# potencia.net
KiCad netlist of a schematic drawn in EAGLE
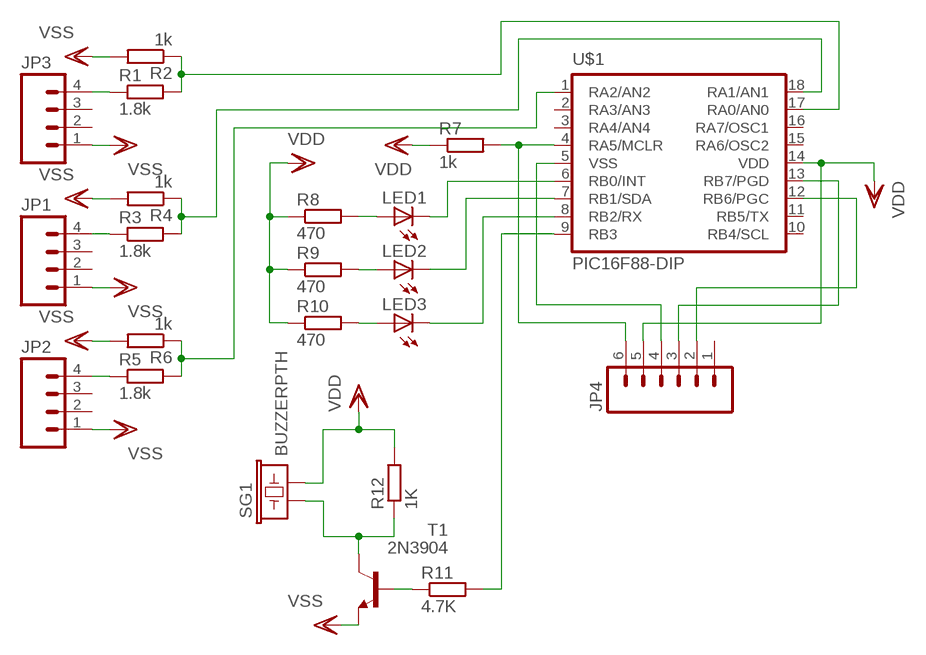
[diagram p0: schematic, sheet 1]
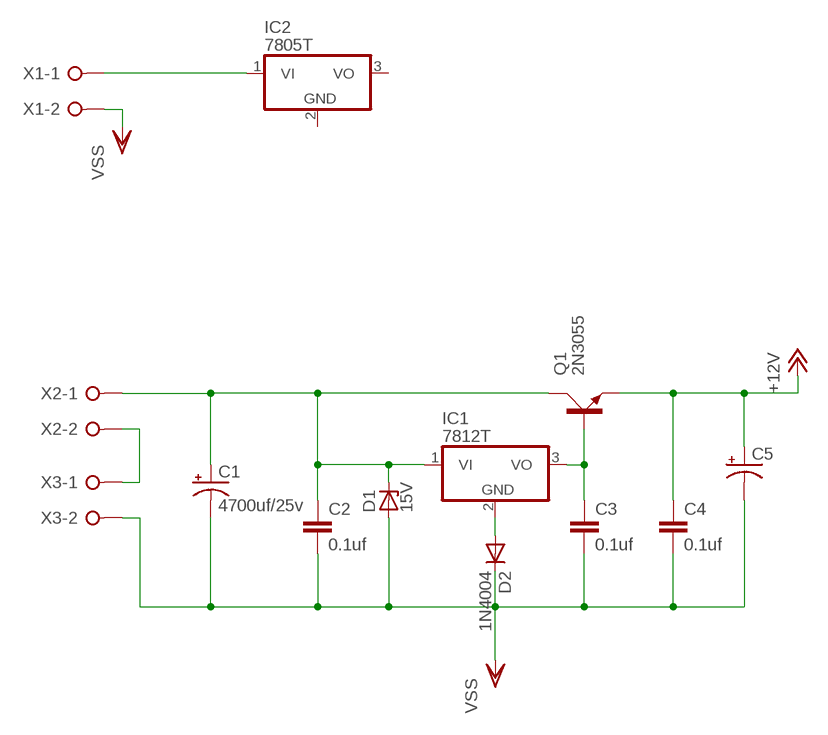
[diagram p1: schematic, sheet 2]

(export (version "E")
  (design (tool "Eeschema 10.0.6"))
  (components
    (comp (ref "C1")
      (value "4700uf/25v")
      (footprint "eagle-import:EB30D")
      (libsource (lib "eagle-import") (part "CPOL-USE10-30"))
    )
    (comp (ref "C2")
      (value "0.1uf")
      (footprint "eagle-import:C050-024X044")
      (libsource (lib "eagle-import") (part "C-EU050-024X044"))
    )
    (comp (ref "C3")
      (value "0.1uf")
      (footprint "eagle-import:C050-024X044")
      (libsource (lib "eagle-import") (part "C-EU050-024X044"))
    )
    (comp (ref "C4")
      (value "0.1uf")
      (footprint "eagle-import:C050-024X044")
      (libsource (lib "eagle-import") (part "C-EU050-024X044"))
    )
    (comp (ref "C5")
      (value "CPOL-USE2.5-6")
      (footprint "eagle-import:E2,5-6")
      (libsource (lib "eagle-import") (part "CPOL-USE2.5-6"))
    )
    (comp (ref "D1")
      (value "15V")
      (footprint "eagle-import:F126Z10")
      (libsource (lib "eagle-import") (part "ZENER-DIODEF126-10"))
    )
    (comp (ref "D2")
      (value "1N4004")
      (footprint "eagle-import:DO41-10")
      (libsource (lib "eagle-import") (part "1N4004"))
    )
    (comp (ref "IC1")
      (value "7812T")
      (footprint "eagle-import:TO220H")
      (libsource (lib "eagle-import") (part "78T12"))
    )
    (comp (ref "IC2")
      (value "7805T")
      (footprint "eagle-import:TO220H")
      (libsource (lib "eagle-import") (part "78T05"))
    )
    (comp (ref "Q1")
      (value "2N3055")
      (footprint "eagle-import:TO3A")
      (libsource (lib "eagle-import") (part "2N3055"))
    )
    (comp (ref "X1")
      (value "W237-2N")
      (footprint "eagle-import:W237-2N")
      (libsource (lib "eagle-import") (part "W237-2N"))
    )
    (comp (ref "X2")
      (value "W237-2N")
      (footprint "eagle-import:W237-2N")
      (libsource (lib "eagle-import") (part "W237-2N"))
    )
    (comp (ref "X3")
      (value "W237-2N")
      (footprint "eagle-import:W237-2N")
      (libsource (lib "eagle-import") (part "W237-2N"))
    )
    (comp (ref "JP1")
      (value "M04LONGPADS")
      (footprint "eagle-import:1X04_LONGPADS")
      (libsource (lib "eagle-import") (part "M04LONGPADS"))
    )
    (comp (ref "JP2")
      (value "M04LONGPADS")
      (footprint "eagle-import:1X04_LONGPADS")
      (libsource (lib "eagle-import") (part "M04LONGPADS"))
    )
    (comp (ref "JP3")
      (value "M04LONGPADS")
      (footprint "eagle-import:1X04_LONGPADS")
      (libsource (lib "eagle-import") (part "M04LONGPADS"))
    )
    (comp (ref "JP4")
      (value "M06LONGPADS")
      (footprint "eagle-import:1X06_LONGPADS")
      (libsource (lib "eagle-import") (part "M06LONGPADS"))
    )
    (comp (ref "LED1")
      (value "LED3MM")
      (footprint "eagle-import:LED3MM")
      (libsource (lib "eagle-import") (part "LED3MM"))
    )
    (comp (ref "LED2")
      (value "LED3MM")
      (footprint "eagle-import:LED3MM")
      (libsource (lib "eagle-import") (part "LED3MM"))
    )
    (comp (ref "LED3")
      (value "LED3MM")
      (footprint "eagle-import:LED3MM")
      (libsource (lib "eagle-import") (part "LED3MM"))
    )
    (comp (ref "R1")
      (value "1.8k")
      (footprint "eagle-import:0204_5")
      (libsource (lib "eagle-import") (part "R-EU_0204/5"))
    )
    (comp (ref "R2")
      (value "1k")
      (footprint "eagle-import:0204_5")
      (libsource (lib "eagle-import") (part "R-EU_0204/5"))
    )
    (comp (ref "R3")
      (value "1.8k")
      (footprint "eagle-import:0204_5")
      (libsource (lib "eagle-import") (part "R-EU_0204/5"))
    )
    (comp (ref "R4")
      (value "1k")
      (footprint "eagle-import:0204_5")
      (libsource (lib "eagle-import") (part "R-EU_0204/5"))
    )
    (comp (ref "R5")
      (value "1.8k")
      (footprint "eagle-import:0204_5")
      (libsource (lib "eagle-import") (part "R-EU_0204/5"))
    )
    (comp (ref "R6")
      (value "1k")
      (footprint "eagle-import:0204_5")
      (libsource (lib "eagle-import") (part "R-EU_0204/5"))
    )
    (comp (ref "R7")
      (value "1k")
      (footprint "eagle-import:0204_5")
      (libsource (lib "eagle-import") (part "R-EU_0204/5"))
    )
    (comp (ref "R8")
      (value "470")
      (footprint "eagle-import:0204_5")
      (libsource (lib "eagle-import") (part "R-EU_0204/5"))
    )
    (comp (ref "R9")
      (value "470")
      (footprint "eagle-import:0204_5")
      (libsource (lib "eagle-import") (part "R-EU_0204/5"))
    )
    (comp (ref "R10")
      (value "470")
      (footprint "eagle-import:0204_5")
      (libsource (lib "eagle-import") (part "R-EU_0204/5"))
    )
    (comp (ref "R11")
      (value "4.7K")
      (footprint "eagle-import:0204_5")
      (libsource (lib "eagle-import") (part "R-EU_0204/5"))
    )
    (comp (ref "R12")
      (value "1K")
      (footprint "eagle-import:0204_5")
      (libsource (lib "eagle-import") (part "R-EU_0204/5"))
    )
    (comp (ref "SG1")
      (value "BUZZERPTH")
      (footprint "eagle-import:BUZZER-12MM")
      (libsource (lib "eagle-import") (part "BUZZERPTH"))
    )
    (comp (ref "T1")
      (value "2N3904")
      (footprint "eagle-import:TO92")
      (libsource (lib "eagle-import") (part "2N3904"))
    )
    (comp (ref "U$1")
      (value "PIC16F88-DIP")
      (footprint "eagle-import:DIL18")
      (libsource (lib "eagle-import") (part "PIC16F88-DIP"))
    )
  )
  (nets
    (net (code "1") (name "+12V") (class "Default")
      (node (ref "C4") (pin "1") (pinfunction "1_1") (pintype "passive"))
      (node (ref "C5") (pin "+") (pinfunction "+_+") (pintype "passive"))
      (node (ref "Q1") (pin "E") (pinfunction "E_E") (pintype "passive"))
    )
    (net (code "2") (name "Net-(IC1-GND)") (class "Default")
      (node (ref "D2") (pin "A") (pinfunction "A_A") (pintype "passive"))
      (node (ref "IC1") (pin "2") (pinfunction "GND_2") (pintype "passive"))
    )
    (net (code "3") (name "Net-(IC1-VI)") (class "Default")
      (node (ref "C1") (pin "+") (pinfunction "+_+") (pintype "passive"))
      (node (ref "C2") (pin "1") (pinfunction "1_1") (pintype "passive"))
      (node (ref "D1") (pin "C") (pinfunction "C_C") (pintype "passive"))
      (node (ref "IC1") (pin "1") (pinfunction "VI_1") (pintype "input"))
      (node (ref "Q1") (pin "C") (pinfunction "C_C") (pintype "passive"))
      (node (ref "Q1") (pin "C1") (pinfunction "C_C1") (pintype "passive"))
      (node (ref "X2") (pin "1") (pinfunction "KL_1") (pintype "passive"))
    )
    (net (code "4") (name "Net-(IC1-VO)") (class "Default")
      (node (ref "C3") (pin "1") (pinfunction "1_1") (pintype "passive"))
      (node (ref "IC1") (pin "3") (pinfunction "VO_3") (pintype "passive"))
      (node (ref "Q1") (pin "B") (pinfunction "B_B") (pintype "passive"))
    )
    (net (code "5") (name "Net-(IC2-VI)") (class "Default")
      (node (ref "IC2") (pin "1") (pinfunction "VI_1") (pintype "input"))
      (node (ref "X1") (pin "1") (pinfunction "KL_1") (pintype "passive"))
    )
    (net (code "6") (name "Net-(JP1-Pad4)") (class "Default")
      (node (ref "JP1") (pin "4") (pinfunction "4_4") (pintype "passive"))
      (node (ref "R3") (pin "1") (pinfunction "1_1") (pintype "passive"))
    )
    (net (code "7") (name "Net-(JP2-Pad4)") (class "Default")
      (node (ref "JP2") (pin "4") (pinfunction "4_4") (pintype "passive"))
      (node (ref "R5") (pin "1") (pinfunction "1_1") (pintype "passive"))
    )
    (net (code "8") (name "Net-(JP3-Pad4)") (class "Default")
      (node (ref "JP3") (pin "4") (pinfunction "4_4") (pintype "passive"))
      (node (ref "R1") (pin "1") (pinfunction "1_1") (pintype "passive"))
    )
    (net (code "9") (name "Net-(LED1-C)") (class "Default")
      (node (ref "LED1") (pin "K") (pinfunction "C_K") (pintype "passive"))
      (node (ref "U$1") (pin "6") (pinfunction "RB0/INT_6") (pintype "bidirectional"))
    )
    (net (code "10") (name "Net-(LED1-PadA)") (class "Default")
      (node (ref "LED1") (pin "A") (pinfunction "A_A") (pintype "passive"))
      (node (ref "R8") (pin "2") (pinfunction "2_2") (pintype "passive"))
    )
    (net (code "11") (name "Net-(LED2-C)") (class "Default")
      (node (ref "LED2") (pin "K") (pinfunction "C_K") (pintype "passive"))
      (node (ref "U$1") (pin "7") (pinfunction "RB1/SDA_7") (pintype "bidirectional"))
    )
    (net (code "12") (name "Net-(LED2-PadA)") (class "Default")
      (node (ref "LED2") (pin "A") (pinfunction "A_A") (pintype "passive"))
      (node (ref "R9") (pin "2") (pinfunction "2_2") (pintype "passive"))
    )
    (net (code "13") (name "Net-(LED3-C)") (class "Default")
      (node (ref "LED3") (pin "K") (pinfunction "C_K") (pintype "passive"))
      (node (ref "U$1") (pin "8") (pinfunction "RB2/RX_8") (pintype "bidirectional"))
    )
    (net (code "14") (name "Net-(LED3-PadA)") (class "Default")
      (node (ref "LED3") (pin "A") (pinfunction "A_A") (pintype "passive"))
      (node (ref "R10") (pin "2") (pinfunction "2_2") (pintype "passive"))
    )
    (net (code "15") (name "Net-(SG1-1)") (class "Default")
      (node (ref "R12") (pin "1") (pinfunction "1_1") (pintype "passive"))
      (node (ref "SG1") (pin "+") (pinfunction "1_+") (pintype "passive"))
      (node (ref "T1") (pin "1") (pinfunction "C_1") (pintype "passive"))
    )
    (net (code "16") (name "Net-(T1-B)") (class "Default")
      (node (ref "R11") (pin "1") (pinfunction "1_1") (pintype "passive"))
      (node (ref "T1") (pin "2") (pinfunction "B_2") (pintype "passive"))
    )
    (net (code "17") (name "Net-(U$1-RA0{slash}AN0)") (class "Default")
      (node (ref "R1") (pin "2") (pinfunction "2_2") (pintype "passive"))
      (node (ref "R2") (pin "1") (pinfunction "1_1") (pintype "passive"))
      (node (ref "U$1") (pin "17") (pinfunction "RA0/AN0_17") (pintype "bidirectional"))
    )
    (net (code "18") (name "Net-(U$1-RA1{slash}AN1)") (class "Default")
      (node (ref "R3") (pin "2") (pinfunction "2_2") (pintype "passive"))
      (node (ref "R4") (pin "1") (pinfunction "1_1") (pintype "passive"))
      (node (ref "U$1") (pin "18") (pinfunction "RA1/AN1_18") (pintype "bidirectional"))
    )
    (net (code "19") (name "Net-(U$1-RA2{slash}AN2)") (class "Default")
      (node (ref "R5") (pin "2") (pinfunction "2_2") (pintype "passive"))
      (node (ref "R6") (pin "1") (pinfunction "1_1") (pintype "passive"))
      (node (ref "U$1") (pin "1") (pinfunction "RA2/AN2_1") (pintype "bidirectional"))
    )
    (net (code "20") (name "Net-(U$1-RA5{slash}MCLR)") (class "Default")
      (node (ref "JP4") (pin "6") (pinfunction "6_6") (pintype "passive"))
      (node (ref "R7") (pin "2") (pinfunction "2_2") (pintype "passive"))
      (node (ref "U$1") (pin "4") (pinfunction "RA5/MCLR_4") (pintype "input"))
    )
    (net (code "21") (name "Net-(U$1-RB3)") (class "Default")
      (node (ref "R11") (pin "2") (pinfunction "2_2") (pintype "passive"))
      (node (ref "U$1") (pin "9") (pinfunction "RB3_9") (pintype "bidirectional"))
    )
    (net (code "22") (name "Net-(U$1-RB6{slash}PGC)") (class "Default")
      (node (ref "JP4") (pin "2") (pinfunction "2_2") (pintype "passive"))
      (node (ref "U$1") (pin "12") (pinfunction "RB6/PGC_12") (pintype "bidirectional"))
    )
    (net (code "23") (name "Net-(U$1-RB7{slash}PGD)") (class "Default")
      (node (ref "JP4") (pin "3") (pinfunction "3_3") (pintype "passive"))
      (node (ref "U$1") (pin "13") (pinfunction "RB7/PGD_13") (pintype "bidirectional"))
    )
    (net (code "24") (name "Net-(U$1-VSS)") (class "Default")
      (node (ref "JP4") (pin "4") (pinfunction "4_4") (pintype "passive"))
      (node (ref "U$1") (pin "5") (pinfunction "VSS_5") (pintype "power_in"))
    )
    (net (code "25") (name "Net-(X2B-KL)") (class "Default")
      (node (ref "X2") (pin "2") (pinfunction "KL_2") (pintype "passive"))
      (node (ref "X3") (pin "1") (pinfunction "KL_1") (pintype "passive"))
    )
    (net (code "26") (name "VDD") (class "Default")
      (node (ref "JP4") (pin "5") (pinfunction "5_5") (pintype "passive"))
      (node (ref "R10") (pin "1") (pinfunction "1_1") (pintype "passive"))
      (node (ref "R12") (pin "2") (pinfunction "2_2") (pintype "passive"))
      (node (ref "R7") (pin "1") (pinfunction "1_1") (pintype "passive"))
      (node (ref "R8") (pin "1") (pinfunction "1_1") (pintype "passive"))
      (node (ref "R9") (pin "1") (pinfunction "1_1") (pintype "passive"))
      (node (ref "SG1") (pin "-") (pinfunction "2_-") (pintype "passive"))
      (node (ref "U$1") (pin "14") (pinfunction "VDD_14") (pintype "power_in"))
    )
    (net (code "27") (name "VSS") (class "Default")
      (node (ref "C1") (pin "-") (pinfunction "-_-") (pintype "passive"))
      (node (ref "C2") (pin "2") (pinfunction "2_2") (pintype "passive"))
      (node (ref "C3") (pin "2") (pinfunction "2_2") (pintype "passive"))
      (node (ref "C4") (pin "2") (pinfunction "2_2") (pintype "passive"))
      (node (ref "C5") (pin "-") (pinfunction "-_-") (pintype "passive"))
      (node (ref "D1") (pin "A") (pinfunction "A_A") (pintype "passive"))
      (node (ref "D2") (pin "C") (pinfunction "C_C") (pintype "passive"))
      (node (ref "JP1") (pin "1") (pinfunction "1_1") (pintype "passive"))
      (node (ref "JP2") (pin "1") (pinfunction "1_1") (pintype "passive"))
      (node (ref "JP3") (pin "1") (pinfunction "1_1") (pintype "passive"))
      (node (ref "R2") (pin "2") (pinfunction "2_2") (pintype "passive"))
      (node (ref "R4") (pin "2") (pinfunction "2_2") (pintype "passive"))
      (node (ref "R6") (pin "2") (pinfunction "2_2") (pintype "passive"))
      (node (ref "T1") (pin "3") (pinfunction "E_3") (pintype "passive"))
      (node (ref "X1") (pin "2") (pinfunction "KL_2") (pintype "passive"))
      (node (ref "X3") (pin "2") (pinfunction "KL_2") (pintype "passive"))
    )
    (net (code "28") (name "unconnected-(IC2-GND-Pad2)") (class "Default")
      (node (ref "IC2") (pin "2") (pinfunction "GND_2") (pintype "passive"))
    )
    (net (code "29") (name "unconnected-(IC2-VO-Pad3)") (class "Default")
      (node (ref "IC2") (pin "3") (pinfunction "VO_3") (pintype "passive"))
    )
    (net (code "30") (name "unconnected-(JP1-Pad2)") (class "Default")
      (node (ref "JP1") (pin "2") (pinfunction "2_2") (pintype "passive"))
    )
    (net (code "31") (name "unconnected-(JP1-Pad3)") (class "Default")
      (node (ref "JP1") (pin "3") (pinfunction "3_3") (pintype "passive"))
    )
    (net (code "32") (name "unconnected-(JP2-Pad2)") (class "Default")
      (node (ref "JP2") (pin "2") (pinfunction "2_2") (pintype "passive"))
    )
    (net (code "33") (name "unconnected-(JP2-Pad3)") (class "Default")
      (node (ref "JP2") (pin "3") (pinfunction "3_3") (pintype "passive"))
    )
    (net (code "34") (name "unconnected-(JP3-Pad2)") (class "Default")
      (node (ref "JP3") (pin "2") (pinfunction "2_2") (pintype "passive"))
    )
    (net (code "35") (name "unconnected-(JP3-Pad3)") (class "Default")
      (node (ref "JP3") (pin "3") (pinfunction "3_3") (pintype "passive"))
    )
    (net (code "36") (name "unconnected-(JP4-Pad1)") (class "Default")
      (node (ref "JP4") (pin "1") (pinfunction "1_1") (pintype "passive"))
    )
    (net (code "37") (name "unconnected-(U$1-RA3{slash}AN3-Pad2)") (class "Default")
      (node (ref "U$1") (pin "2") (pinfunction "RA3/AN3_2") (pintype "bidirectional"))
    )
    (net (code "38") (name "unconnected-(U$1-RA4{slash}AN4-Pad3)") (class "Default")
      (node (ref "U$1") (pin "3") (pinfunction "RA4/AN4_3") (pintype "bidirectional"))
    )
    (net (code "39") (name "unconnected-(U$1-RA6{slash}OSC2-Pad15)") (class "Default")
      (node (ref "U$1") (pin "15") (pinfunction "RA6/OSC2_15") (pintype "bidirectional"))
    )
    (net (code "40") (name "unconnected-(U$1-RA7{slash}OSC1-Pad16)") (class "Default")
      (node (ref "U$1") (pin "16") (pinfunction "RA7/OSC1_16") (pintype "bidirectional"))
    )
    (net (code "41") (name "unconnected-(U$1-RB4{slash}SCL-Pad10)") (class "Default")
      (node (ref "U$1") (pin "10") (pinfunction "RB4/SCL_10") (pintype "bidirectional"))
    )
    (net (code "42") (name "unconnected-(U$1-RB5{slash}TX-Pad11)") (class "Default")
      (node (ref "U$1") (pin "11") (pinfunction "RB5/TX_11") (pintype "bidirectional"))
    )
  )
)
